# z.net
KiCad netlist of a schematic drawn in EAGLE
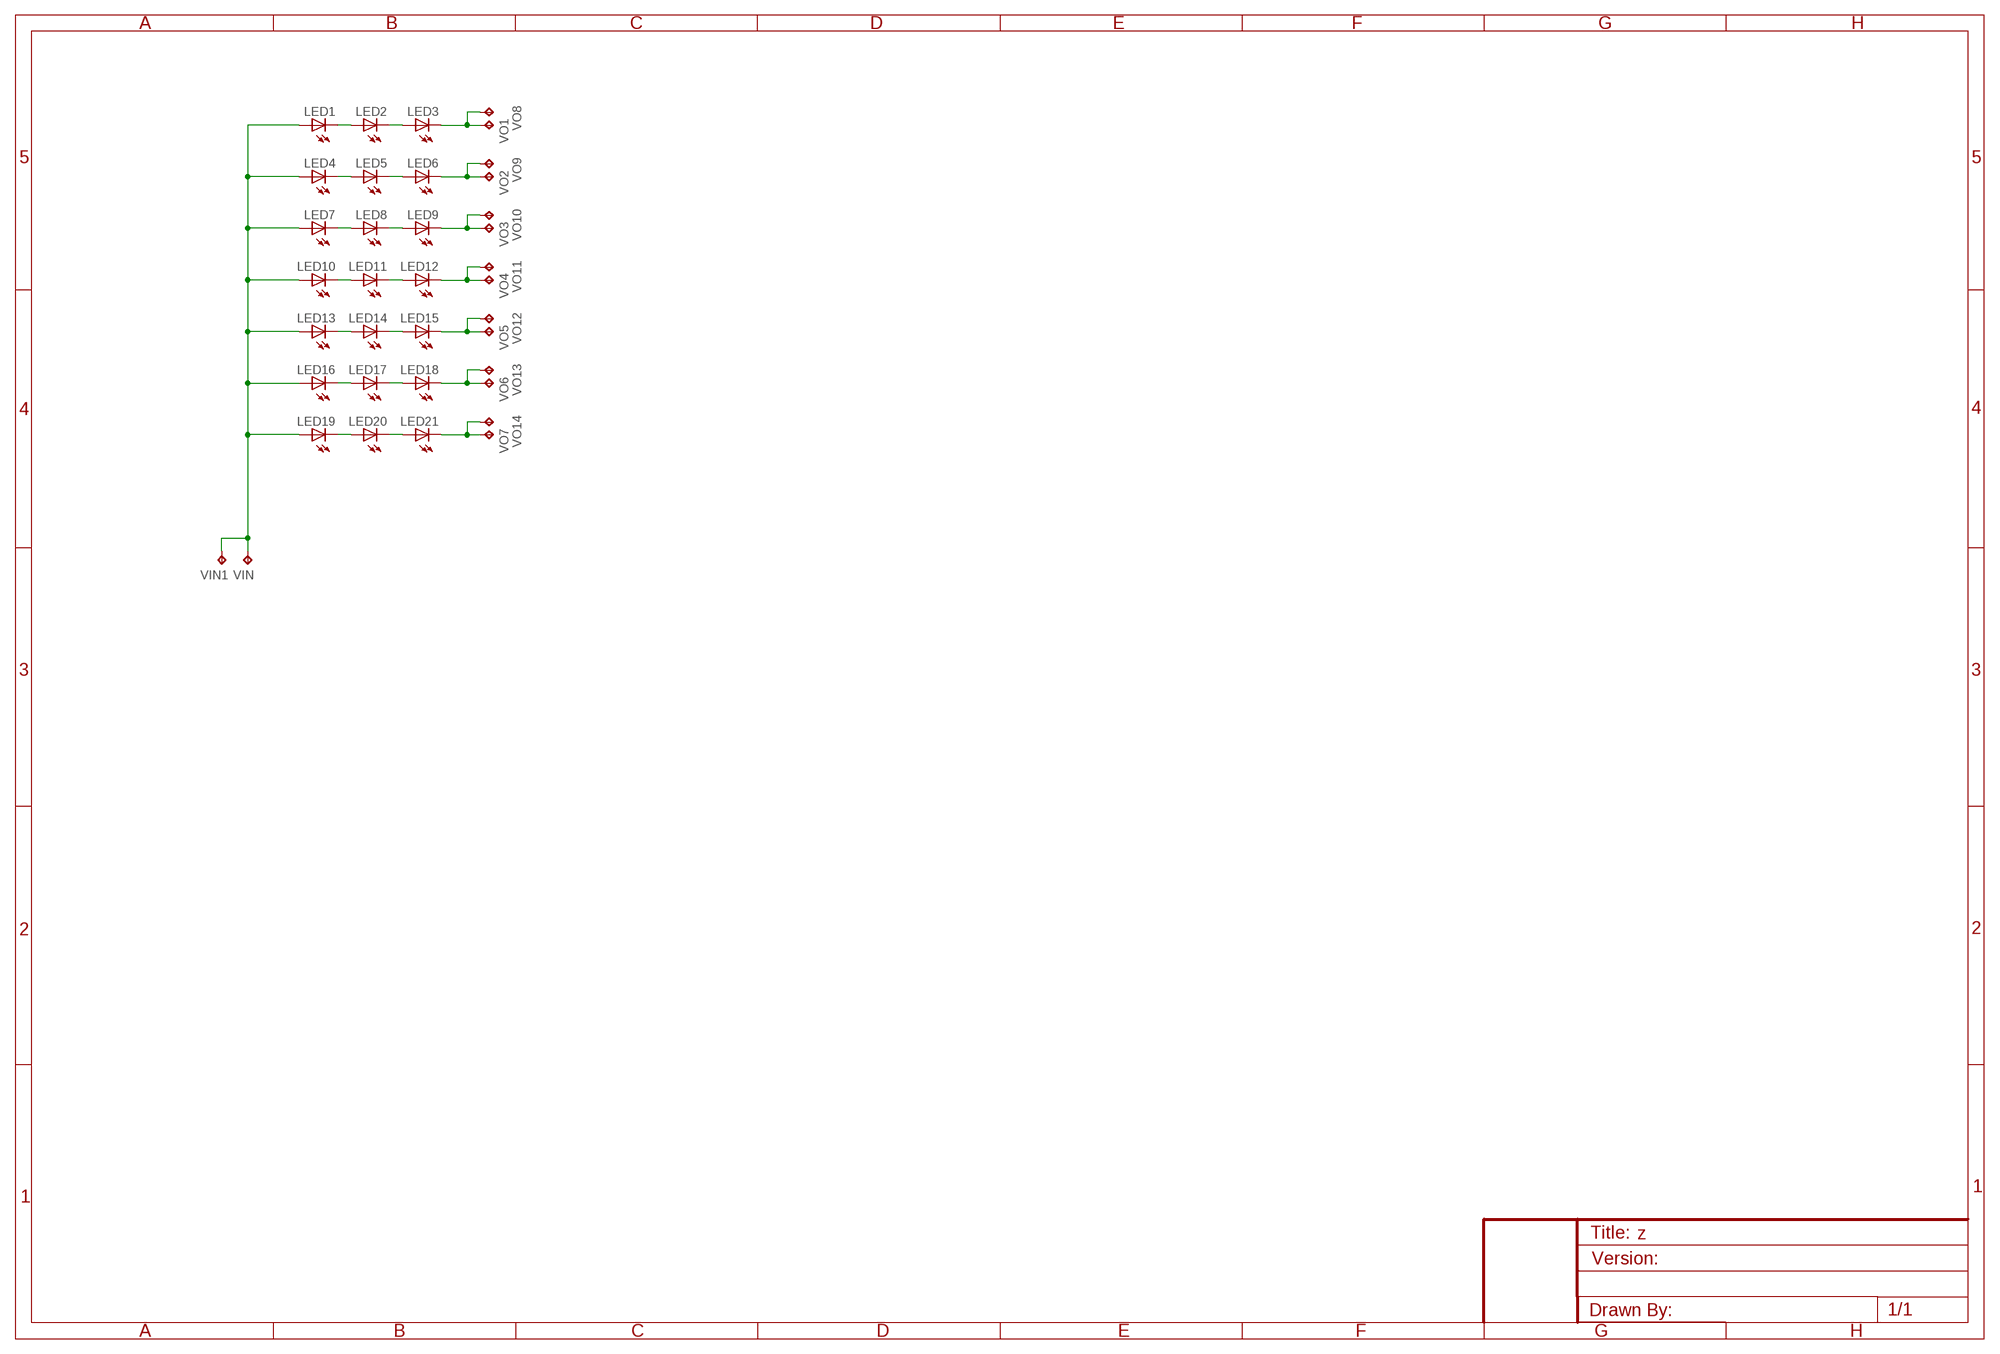
[diagram p0: schematic, sheet 1]

(export (version "E")
  (design (tool "Eeschema 10.0.6"))
  (components
    (comp (ref "LED1")
      (value "LED0805")
      (footprint "eagle-import:LED_0805")
      (libsource (lib "eagle-import") (part "LED0805"))
    )
    (comp (ref "LED2")
      (value "LED0805")
      (footprint "eagle-import:LED_0805")
      (libsource (lib "eagle-import") (part "LED0805"))
    )
    (comp (ref "LED3")
      (value "LED0805")
      (footprint "eagle-import:LED_0805")
      (libsource (lib "eagle-import") (part "LED0805"))
    )
    (comp (ref "LED4")
      (value "LED0805")
      (footprint "eagle-import:LED_0805")
      (libsource (lib "eagle-import") (part "LED0805"))
    )
    (comp (ref "LED5")
      (value "LED0805")
      (footprint "eagle-import:LED_0805")
      (libsource (lib "eagle-import") (part "LED0805"))
    )
    (comp (ref "LED6")
      (value "LED0805")
      (footprint "eagle-import:LED_0805")
      (libsource (lib "eagle-import") (part "LED0805"))
    )
    (comp (ref "LED7")
      (value "LED0805")
      (footprint "eagle-import:LED_0805")
      (libsource (lib "eagle-import") (part "LED0805"))
    )
    (comp (ref "LED8")
      (value "LED0805")
      (footprint "eagle-import:LED_0805")
      (libsource (lib "eagle-import") (part "LED0805"))
    )
    (comp (ref "LED9")
      (value "LED0805")
      (footprint "eagle-import:LED_0805")
      (libsource (lib "eagle-import") (part "LED0805"))
    )
    (comp (ref "LED10")
      (value "LED0805")
      (footprint "eagle-import:LED_0805")
      (libsource (lib "eagle-import") (part "LED0805"))
    )
    (comp (ref "LED11")
      (value "LED0805")
      (footprint "eagle-import:LED_0805")
      (libsource (lib "eagle-import") (part "LED0805"))
    )
    (comp (ref "LED12")
      (value "LED0805")
      (footprint "eagle-import:LED_0805")
      (libsource (lib "eagle-import") (part "LED0805"))
    )
    (comp (ref "LED13")
      (value "LED0805")
      (footprint "eagle-import:LED_0805")
      (libsource (lib "eagle-import") (part "LED0805"))
    )
    (comp (ref "LED14")
      (value "LED0805")
      (footprint "eagle-import:LED_0805")
      (libsource (lib "eagle-import") (part "LED0805"))
    )
    (comp (ref "LED15")
      (value "LED0805")
      (footprint "eagle-import:LED_0805")
      (libsource (lib "eagle-import") (part "LED0805"))
    )
    (comp (ref "LED16")
      (value "LED0805")
      (footprint "eagle-import:LED_0805")
      (libsource (lib "eagle-import") (part "LED0805"))
    )
    (comp (ref "LED17")
      (value "LED0805")
      (footprint "eagle-import:LED_0805")
      (libsource (lib "eagle-import") (part "LED0805"))
    )
    (comp (ref "LED18")
      (value "LED0805")
      (footprint "eagle-import:LED_0805")
      (libsource (lib "eagle-import") (part "LED0805"))
    )
    (comp (ref "LED19")
      (value "LED0805")
      (footprint "eagle-import:LED_0805")
      (libsource (lib "eagle-import") (part "LED0805"))
    )
    (comp (ref "LED20")
      (value "LED0805")
      (footprint "eagle-import:LED_0805")
      (libsource (lib "eagle-import") (part "LED0805"))
    )
    (comp (ref "LED21")
      (value "LED0805")
      (footprint "eagle-import:LED_0805")
      (libsource (lib "eagle-import") (part "LED0805"))
    )
    (comp (ref "VIN")
      (value "TEST_POINTPAD1-20")
      (footprint "eagle-import:P1-20")
      (libsource (lib "eagle-import") (part "TEST_POINTPAD1-20"))
    )
    (comp (ref "VIN1")
      (value "TEST_POINTPAD1-20")
      (footprint "eagle-import:P1-20")
      (libsource (lib "eagle-import") (part "TEST_POINTPAD1-20"))
    )
    (comp (ref "VO1")
      (value "TEST_POINTPAD1-20")
      (footprint "eagle-import:P1-20")
      (libsource (lib "eagle-import") (part "TEST_POINTPAD1-20"))
    )
    (comp (ref "VO2")
      (value "TEST_POINTPAD1-20")
      (footprint "eagle-import:P1-20")
      (libsource (lib "eagle-import") (part "TEST_POINTPAD1-20"))
    )
    (comp (ref "VO3")
      (value "TEST_POINTPAD1-20")
      (footprint "eagle-import:P1-20")
      (libsource (lib "eagle-import") (part "TEST_POINTPAD1-20"))
    )
    (comp (ref "VO4")
      (value "TEST_POINTPAD1-20")
      (footprint "eagle-import:P1-20")
      (libsource (lib "eagle-import") (part "TEST_POINTPAD1-20"))
    )
    (comp (ref "VO5")
      (value "TEST_POINTPAD1-20")
      (footprint "eagle-import:P1-20")
      (libsource (lib "eagle-import") (part "TEST_POINTPAD1-20"))
    )
    (comp (ref "VO6")
      (value "TEST_POINTPAD1-20")
      (footprint "eagle-import:P1-20")
      (libsource (lib "eagle-import") (part "TEST_POINTPAD1-20"))
    )
    (comp (ref "VO7")
      (value "TEST_POINTPAD1-20")
      (footprint "eagle-import:P1-20")
      (libsource (lib "eagle-import") (part "TEST_POINTPAD1-20"))
    )
    (comp (ref "VO8")
      (value "TEST_POINTPAD1-20")
      (footprint "eagle-import:P1-20")
      (libsource (lib "eagle-import") (part "TEST_POINTPAD1-20"))
    )
    (comp (ref "VO9")
      (value "TEST_POINTPAD1-20")
      (footprint "eagle-import:P1-20")
      (libsource (lib "eagle-import") (part "TEST_POINTPAD1-20"))
    )
    (comp (ref "VO10")
      (value "TEST_POINTPAD1-20")
      (footprint "eagle-import:P1-20")
      (libsource (lib "eagle-import") (part "TEST_POINTPAD1-20"))
    )
    (comp (ref "VO11")
      (value "TEST_POINTPAD1-20")
      (footprint "eagle-import:P1-20")
      (libsource (lib "eagle-import") (part "TEST_POINTPAD1-20"))
    )
    (comp (ref "VO12")
      (value "TEST_POINTPAD1-20")
      (footprint "eagle-import:P1-20")
      (libsource (lib "eagle-import") (part "TEST_POINTPAD1-20"))
    )
    (comp (ref "VO13")
      (value "TEST_POINTPAD1-20")
      (footprint "eagle-import:P1-20")
      (libsource (lib "eagle-import") (part "TEST_POINTPAD1-20"))
    )
    (comp (ref "VO14")
      (value "TEST_POINTPAD1-20")
      (footprint "eagle-import:P1-20")
      (libsource (lib "eagle-import") (part "TEST_POINTPAD1-20"))
    )
  )
  (nets
    (net (code "1") (name "Net-(LED1-PadA)") (class "Default")
      (node (ref "LED1") (pin "A") (pinfunction "A_A") (pintype "passive"))
      (node (ref "LED10") (pin "A") (pinfunction "A_A") (pintype "passive"))
      (node (ref "LED13") (pin "A") (pinfunction "A_A") (pintype "passive"))
      (node (ref "LED16") (pin "A") (pinfunction "A_A") (pintype "passive"))
      (node (ref "LED19") (pin "A") (pinfunction "A_A") (pintype "passive"))
      (node (ref "LED4") (pin "A") (pinfunction "A_A") (pintype "passive"))
      (node (ref "LED7") (pin "A") (pinfunction "A_A") (pintype "passive"))
      (node (ref "VIN") (pin "TP") (pinfunction "TP_TP") (pintype "input"))
      (node (ref "VIN1") (pin "TP") (pinfunction "TP_TP") (pintype "input"))
    )
    (net (code "2") (name "Net-(LED1-PadC)") (class "Default")
      (node (ref "LED1") (pin "C") (pinfunction "C_C") (pintype "passive"))
      (node (ref "LED2") (pin "A") (pinfunction "A_A") (pintype "passive"))
    )
    (net (code "3") (name "Net-(LED2-PadC)") (class "Default")
      (node (ref "LED2") (pin "C") (pinfunction "C_C") (pintype "passive"))
      (node (ref "LED3") (pin "A") (pinfunction "A_A") (pintype "passive"))
    )
    (net (code "4") (name "Net-(LED3-PadC)") (class "Default")
      (node (ref "LED3") (pin "C") (pinfunction "C_C") (pintype "passive"))
      (node (ref "VO1") (pin "TP") (pinfunction "TP_TP") (pintype "input"))
      (node (ref "VO8") (pin "TP") (pinfunction "TP_TP") (pintype "input"))
    )
    (net (code "5") (name "Net-(LED4-PadC)") (class "Default")
      (node (ref "LED4") (pin "C") (pinfunction "C_C") (pintype "passive"))
      (node (ref "LED5") (pin "A") (pinfunction "A_A") (pintype "passive"))
    )
    (net (code "6") (name "Net-(LED5-PadC)") (class "Default")
      (node (ref "LED5") (pin "C") (pinfunction "C_C") (pintype "passive"))
      (node (ref "LED6") (pin "A") (pinfunction "A_A") (pintype "passive"))
    )
    (net (code "7") (name "Net-(LED6-PadC)") (class "Default")
      (node (ref "LED6") (pin "C") (pinfunction "C_C") (pintype "passive"))
      (node (ref "VO2") (pin "TP") (pinfunction "TP_TP") (pintype "input"))
      (node (ref "VO9") (pin "TP") (pinfunction "TP_TP") (pintype "input"))
    )
    (net (code "8") (name "Net-(LED7-PadC)") (class "Default")
      (node (ref "LED7") (pin "C") (pinfunction "C_C") (pintype "passive"))
      (node (ref "LED8") (pin "A") (pinfunction "A_A") (pintype "passive"))
    )
    (net (code "9") (name "Net-(LED8-PadC)") (class "Default")
      (node (ref "LED8") (pin "C") (pinfunction "C_C") (pintype "passive"))
      (node (ref "LED9") (pin "A") (pinfunction "A_A") (pintype "passive"))
    )
    (net (code "10") (name "Net-(LED9-PadC)") (class "Default")
      (node (ref "LED9") (pin "C") (pinfunction "C_C") (pintype "passive"))
      (node (ref "VO10") (pin "TP") (pinfunction "TP_TP") (pintype "input"))
      (node (ref "VO3") (pin "TP") (pinfunction "TP_TP") (pintype "input"))
    )
    (net (code "11") (name "Net-(LED10-PadC)") (class "Default")
      (node (ref "LED10") (pin "C") (pinfunction "C_C") (pintype "passive"))
      (node (ref "LED11") (pin "A") (pinfunction "A_A") (pintype "passive"))
    )
    (net (code "12") (name "Net-(LED11-PadC)") (class "Default")
      (node (ref "LED11") (pin "C") (pinfunction "C_C") (pintype "passive"))
      (node (ref "LED12") (pin "A") (pinfunction "A_A") (pintype "passive"))
    )
    (net (code "13") (name "Net-(LED12-PadC)") (class "Default")
      (node (ref "LED12") (pin "C") (pinfunction "C_C") (pintype "passive"))
      (node (ref "VO11") (pin "TP") (pinfunction "TP_TP") (pintype "input"))
      (node (ref "VO4") (pin "TP") (pinfunction "TP_TP") (pintype "input"))
    )
    (net (code "14") (name "Net-(LED13-PadC)") (class "Default")
      (node (ref "LED13") (pin "C") (pinfunction "C_C") (pintype "passive"))
      (node (ref "LED14") (pin "A") (pinfunction "A_A") (pintype "passive"))
    )
    (net (code "15") (name "Net-(LED14-PadC)") (class "Default")
      (node (ref "LED14") (pin "C") (pinfunction "C_C") (pintype "passive"))
      (node (ref "LED15") (pin "A") (pinfunction "A_A") (pintype "passive"))
    )
    (net (code "16") (name "Net-(LED15-PadC)") (class "Default")
      (node (ref "LED15") (pin "C") (pinfunction "C_C") (pintype "passive"))
      (node (ref "VO12") (pin "TP") (pinfunction "TP_TP") (pintype "input"))
      (node (ref "VO5") (pin "TP") (pinfunction "TP_TP") (pintype "input"))
    )
    (net (code "17") (name "Net-(LED16-PadC)") (class "Default")
      (node (ref "LED16") (pin "C") (pinfunction "C_C") (pintype "passive"))
      (node (ref "LED17") (pin "A") (pinfunction "A_A") (pintype "passive"))
    )
    (net (code "18") (name "Net-(LED17-PadC)") (class "Default")
      (node (ref "LED17") (pin "C") (pinfunction "C_C") (pintype "passive"))
      (node (ref "LED18") (pin "A") (pinfunction "A_A") (pintype "passive"))
    )
    (net (code "19") (name "Net-(LED18-PadC)") (class "Default")
      (node (ref "LED18") (pin "C") (pinfunction "C_C") (pintype "passive"))
      (node (ref "VO13") (pin "TP") (pinfunction "TP_TP") (pintype "input"))
      (node (ref "VO6") (pin "TP") (pinfunction "TP_TP") (pintype "input"))
    )
    (net (code "20") (name "Net-(LED19-PadC)") (class "Default")
      (node (ref "LED19") (pin "C") (pinfunction "C_C") (pintype "passive"))
      (node (ref "LED20") (pin "A") (pinfunction "A_A") (pintype "passive"))
    )
    (net (code "21") (name "Net-(LED20-PadC)") (class "Default")
      (node (ref "LED20") (pin "C") (pinfunction "C_C") (pintype "passive"))
      (node (ref "LED21") (pin "A") (pinfunction "A_A") (pintype "passive"))
    )
    (net (code "22") (name "Net-(LED21-PadC)") (class "Default")
      (node (ref "LED21") (pin "C") (pinfunction "C_C") (pintype "passive"))
      (node (ref "VO14") (pin "TP") (pinfunction "TP_TP") (pintype "input"))
      (node (ref "VO7") (pin "TP") (pinfunction "TP_TP") (pintype "input"))
    )
  )
)
